# Irrigation_Controller.net
KiCad netlist of a schematic drawn in EAGLE
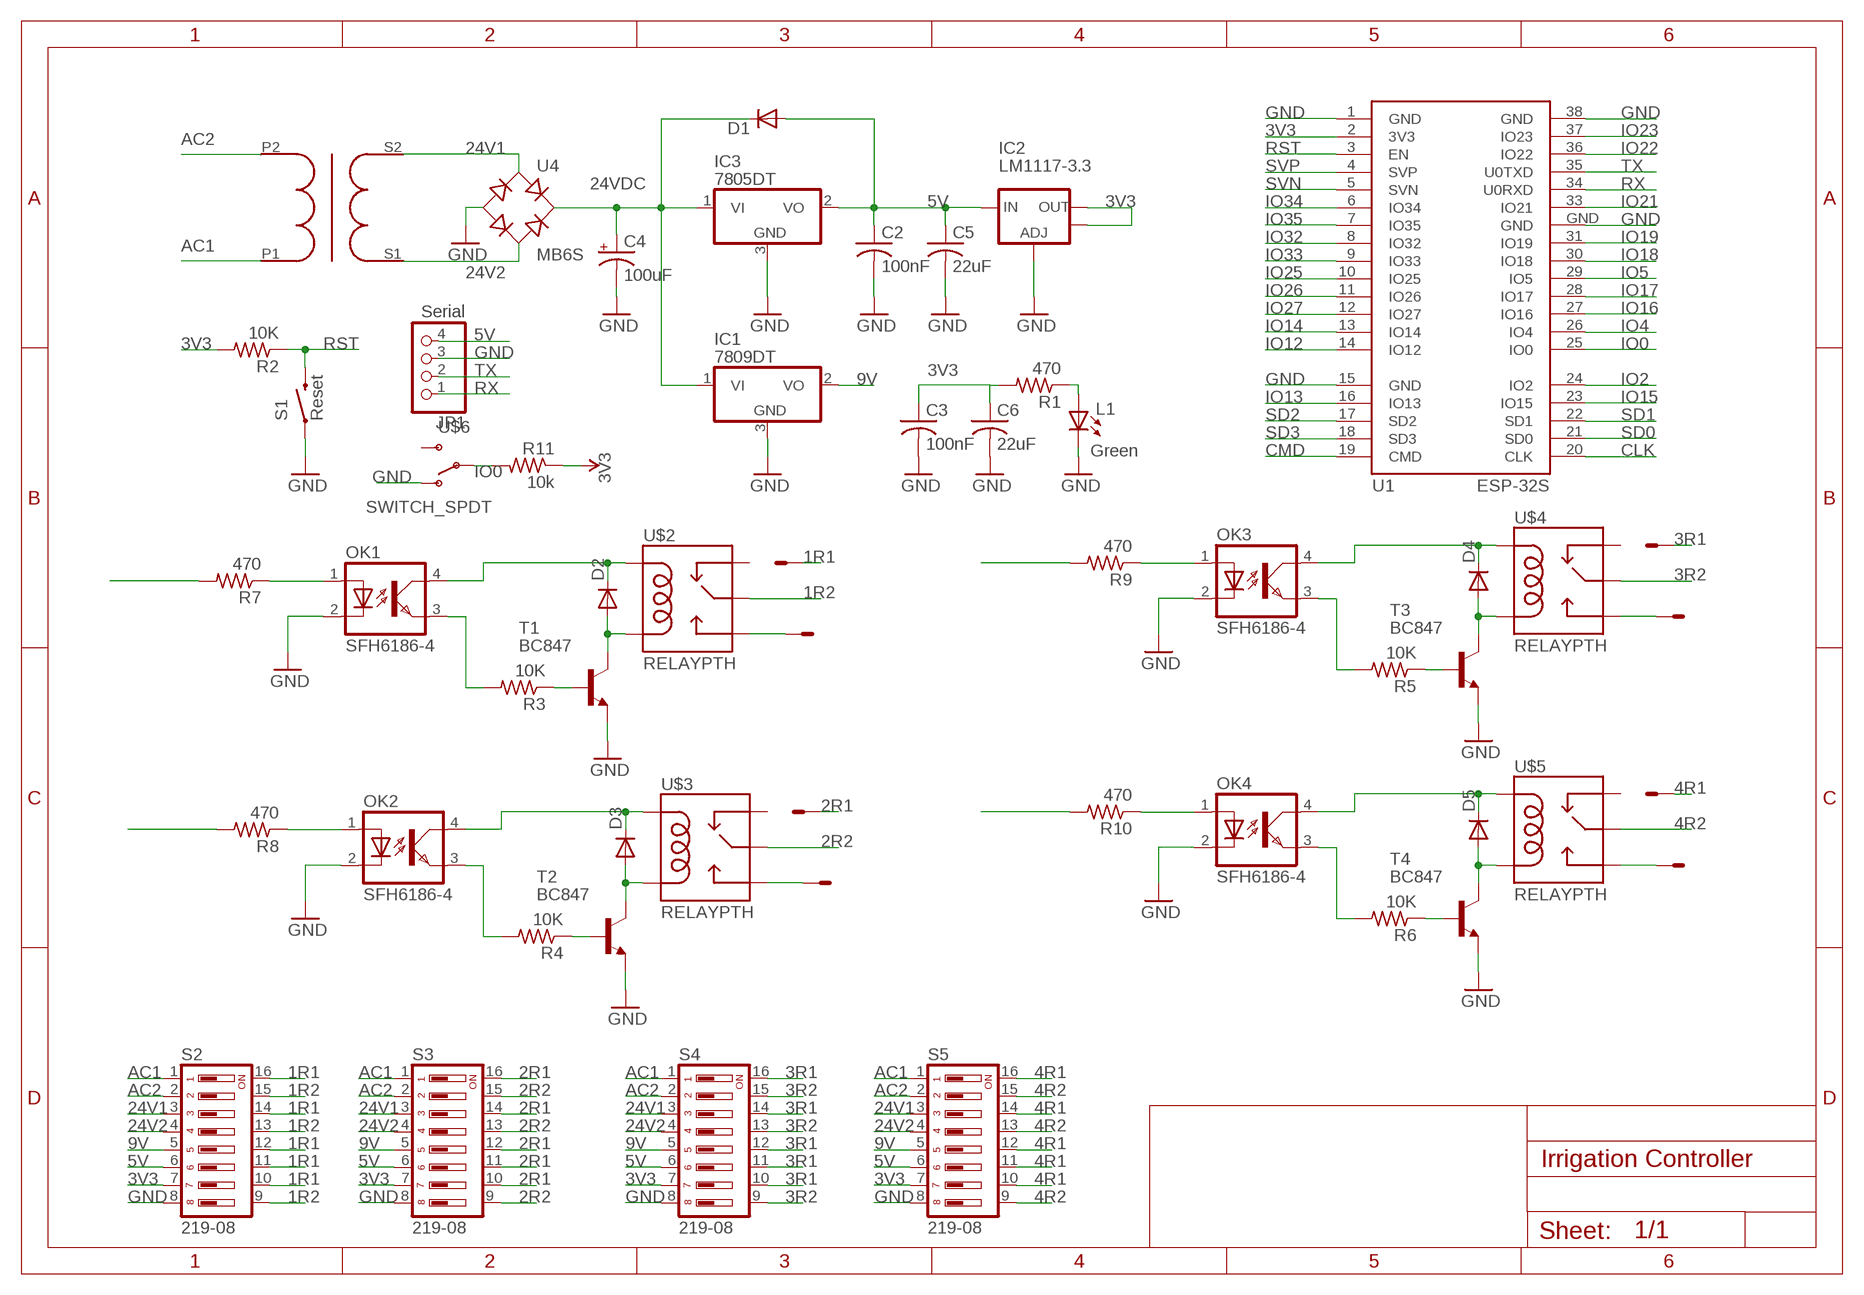
[diagram p0: schematic, sheet 1]

(export (version "E")
  (design (tool "Eeschema 10.0.6"))
  (components
    (comp (ref "C2")
      (value "100nF")
      (footprint "eagle-import:1206")
      (libsource (lib "eagle-import") (part "C1206"))
    )
    (comp (ref "C3")
      (value "100nF")
      (footprint "eagle-import:1206")
      (libsource (lib "eagle-import") (part "C1206"))
    )
    (comp (ref "C4")
      (value "100uF")
      (footprint "eagle-import:CT7343")
      (libsource (lib "eagle-import") (part "CPOL-USCT7343"))
    )
    (comp (ref "C5")
      (value "22uF")
      (footprint "eagle-import:1206")
      (libsource (lib "eagle-import") (part "C1206"))
    )
    (comp (ref "C6")
      (value "22uF")
      (footprint "eagle-import:1206")
      (libsource (lib "eagle-import") (part "C1206"))
    )
    (comp (ref "D1")
      (value "DIODE-SOD123")
      (footprint "eagle-import:SOD123")
      (libsource (lib "eagle-import") (part "DIODE-SOD123"))
    )
    (comp (ref "D2")
      (value "DIODE-SOD123")
      (footprint "eagle-import:SOD123")
      (libsource (lib "eagle-import") (part "DIODE-SOD123"))
    )
    (comp (ref "D3")
      (value "DIODE-SOD123")
      (footprint "eagle-import:SOD123")
      (libsource (lib "eagle-import") (part "DIODE-SOD123"))
    )
    (comp (ref "D4")
      (value "DIODE-SOD123")
      (footprint "eagle-import:SOD123")
      (libsource (lib "eagle-import") (part "DIODE-SOD123"))
    )
    (comp (ref "D5")
      (value "DIODE-SOD123")
      (footprint "eagle-import:SOD123")
      (libsource (lib "eagle-import") (part "DIODE-SOD123"))
    )
    (comp (ref "IC1")
      (value "7809DT")
      (footprint "eagle-import:TO252")
      (libsource (lib "eagle-import") (part "78DT05"))
    )
    (comp (ref "IC2")
      (value "LM1117-3.3")
      (footprint "eagle-import:SOT223")
      (libsource (lib "eagle-import") (part "V_REG_LM1117SOT223"))
    )
    (comp (ref "IC3")
      (value "7805DT")
      (footprint "eagle-import:TO252")
      (libsource (lib "eagle-import") (part "78DT05"))
    )
    (comp (ref "JP1")
      (value "Serial")
      (footprint "eagle-import:1X04")
      (libsource (lib "eagle-import") (part "PINHD-1X4"))
    )
    (comp (ref "L1")
      (value "Green")
      (footprint "eagle-import:LED1206")
      (libsource (lib "eagle-import") (part "LED1206"))
    )
    (comp (ref "OK1")
      (value "SFH6186-4")
      (footprint "eagle-import:SMD4-7")
      (fields (field (name "MF") "VISHAY/TELEFUNKEN"))
      (libsource (lib "eagle-import") (part "SFH618?6-4"))
    )
    (comp (ref "OK2")
      (value "SFH6186-4")
      (footprint "eagle-import:SMD4-7")
      (fields (field (name "MF") "VISHAY/TELEFUNKEN"))
      (libsource (lib "eagle-import") (part "SFH618?6-4"))
    )
    (comp (ref "OK3")
      (value "SFH6186-4")
      (footprint "eagle-import:SMD4-7")
      (fields (field (name "MF") "VISHAY/TELEFUNKEN"))
      (libsource (lib "eagle-import") (part "SFH618?6-4"))
    )
    (comp (ref "OK4")
      (value "SFH6186-4")
      (footprint "eagle-import:SMD4-7")
      (fields (field (name "MF") "VISHAY/TELEFUNKEN"))
      (libsource (lib "eagle-import") (part "SFH618?6-4"))
    )
    (comp (ref "R1")
      (value "470")
      (footprint "eagle-import:1206")
      (libsource (lib "eagle-import") (part "R1206"))
    )
    (comp (ref "R2")
      (value "10K")
      (footprint "eagle-import:R1206")
      (libsource (lib "eagle-import") (part "R-US_R1206"))
    )
    (comp (ref "R3")
      (value "10K")
      (footprint "eagle-import:R1206")
      (libsource (lib "eagle-import") (part "R-US_R1206"))
    )
    (comp (ref "R4")
      (value "10K")
      (footprint "eagle-import:R1206")
      (libsource (lib "eagle-import") (part "R-US_R1206"))
    )
    (comp (ref "R5")
      (value "10K")
      (footprint "eagle-import:R1206")
      (libsource (lib "eagle-import") (part "R-US_R1206"))
    )
    (comp (ref "R6")
      (value "10K")
      (footprint "eagle-import:R1206")
      (libsource (lib "eagle-import") (part "R-US_R1206"))
    )
    (comp (ref "R7")
      (value "470")
      (footprint "eagle-import:R1206")
      (libsource (lib "eagle-import") (part "R-US_R1206"))
    )
    (comp (ref "R8")
      (value "470")
      (footprint "eagle-import:R1206")
      (libsource (lib "eagle-import") (part "R-US_R1206"))
    )
    (comp (ref "R9")
      (value "470")
      (footprint "eagle-import:R1206")
      (libsource (lib "eagle-import") (part "R-US_R1206"))
    )
    (comp (ref "R10")
      (value "470")
      (footprint "eagle-import:R1206")
      (libsource (lib "eagle-import") (part "R-US_R1206"))
    )
    (comp (ref "R11")
      (value "10k")
      (footprint "eagle-import:1206")
      (libsource (lib "eagle-import") (part "R1206"))
    )
    (comp (ref "S1")
      (value "Reset")
      (footprint "eagle-import:TACTILE_SWITCH_TALL")
      (libsource (lib "eagle-import") (part "SWITCH-MOMENTARY-2SMD-4"))
    )
    (comp (ref "S2")
      (value "219-08")
      (footprint "eagle-import:CTS-219-08")
      (libsource (lib "eagle-import") (part "219-08"))
    )
    (comp (ref "S3")
      (value "219-08")
      (footprint "eagle-import:CTS-219-08")
      (libsource (lib "eagle-import") (part "219-08"))
    )
    (comp (ref "S4")
      (value "219-08")
      (footprint "eagle-import:CTS-219-08")
      (libsource (lib "eagle-import") (part "219-08"))
    )
    (comp (ref "S5")
      (value "219-08")
      (footprint "eagle-import:CTS-219-08")
      (libsource (lib "eagle-import") (part "219-08"))
    )
    (comp (ref "T1")
      (value "BC847")
      (footprint "eagle-import:SOT23")
      (libsource (lib "eagle-import") (part "BC847"))
    )
    (comp (ref "T2")
      (value "BC847")
      (footprint "eagle-import:SOT23")
      (libsource (lib "eagle-import") (part "BC847"))
    )
    (comp (ref "T3")
      (value "BC847")
      (footprint "eagle-import:SOT23")
      (libsource (lib "eagle-import") (part "BC847"))
    )
    (comp (ref "T4")
      (value "BC847")
      (footprint "eagle-import:SOT23")
      (libsource (lib "eagle-import") (part "BC847"))
    )
    (comp (ref "U$1")
      (value "TRANSFORMADOR_PE3010-M")
      (footprint "eagle-import:TRANSFORMADOR_PE3010-M")
      (libsource (lib "eagle-import") (part "TRANSFORMADOR_PE3010-M"))
    )
    (comp (ref "U$2")
      (value "RELAYPTH")
      (footprint "eagle-import:SRD-05VDC-SL-C")
      (libsource (lib "eagle-import") (part "RELAYPTH"))
    )
    (comp (ref "U$3")
      (value "RELAYPTH")
      (footprint "eagle-import:SRD-05VDC-SL-C")
      (libsource (lib "eagle-import") (part "RELAYPTH"))
    )
    (comp (ref "U$4")
      (value "RELAYPTH")
      (footprint "eagle-import:SRD-05VDC-SL-C")
      (libsource (lib "eagle-import") (part "RELAYPTH"))
    )
    (comp (ref "U$5")
      (value "RELAYPTH")
      (footprint "eagle-import:SRD-05VDC-SL-C")
      (libsource (lib "eagle-import") (part "RELAYPTH"))
    )
    (comp (ref "U$6")
      (value "SWITCH_SPDT")
      (footprint "eagle-import:KPS-1290")
      (libsource (lib "eagle-import") (part "SWITCH_SPDT"))
    )
    (comp (ref "U1")
      (value "ESP-32S")
      (footprint "eagle-import:ESP-32S")
      (libsource (lib "eagle-import") (part "ESP-32S"))
    )
    (comp (ref "U4")
      (value "MB6S")
      (footprint "eagle-import:SOIC-4")
      (libsource (lib "eagle-import") (part "MBS6"))
    )
    (comp (ref "X1")
      (value "22-23-2021")
      (footprint "eagle-import:22-23-2021")
      (fields (field (name "MF") "MOLEX"))
      (libsource (lib "eagle-import") (part "22-23-2021"))
    )
    (comp (ref "X2")
      (value "22-23-2021")
      (footprint "eagle-import:22-23-2021")
      (fields (field (name "MF") "MOLEX"))
      (libsource (lib "eagle-import") (part "22-23-2021"))
    )
    (comp (ref "X3")
      (value "22-23-2021")
      (footprint "eagle-import:22-23-2021")
      (fields (field (name "MF") "MOLEX"))
      (libsource (lib "eagle-import") (part "22-23-2021"))
    )
    (comp (ref "X4")
      (value "22-23-2021")
      (footprint "eagle-import:22-23-2021")
      (fields (field (name "MF") "MOLEX"))
      (libsource (lib "eagle-import") (part "22-23-2021"))
    )
  )
  (nets
    (net (code "1") (name "/1R1") (class "Default")
      (node (ref "S2") (pin "10") (pinfunction "10_10") (pintype "passive"))
      (node (ref "S2") (pin "11") (pinfunction "11_11") (pintype "passive"))
      (node (ref "S2") (pin "12") (pinfunction "12_12") (pintype "passive"))
      (node (ref "S2") (pin "14") (pinfunction "14_14") (pintype "passive"))
      (node (ref "S2") (pin "16") (pinfunction "16_16") (pintype "passive"))
      (node (ref "X1") (pin "1") (pinfunction "S_1") (pintype "passive"))
    )
    (net (code "2") (name "/1R2") (class "Default")
      (node (ref "S2") (pin "13") (pinfunction "13_13") (pintype "passive"))
      (node (ref "S2") (pin "15") (pinfunction "15_15") (pintype "passive"))
      (node (ref "S2") (pin "9") (pinfunction "9_9") (pintype "passive"))
      (node (ref "U$2") (pin "SWCOMMON") (pinfunction "SWCOMMON_SWCOMMON") (pintype "bidirectional"))
    )
    (net (code "3") (name "/2R1") (class "Default")
      (node (ref "S3") (pin "10") (pinfunction "10_10") (pintype "passive"))
      (node (ref "S3") (pin "11") (pinfunction "11_11") (pintype "passive"))
      (node (ref "S3") (pin "12") (pinfunction "12_12") (pintype "passive"))
      (node (ref "S3") (pin "14") (pinfunction "14_14") (pintype "passive"))
      (node (ref "S3") (pin "16") (pinfunction "16_16") (pintype "passive"))
      (node (ref "X2") (pin "1") (pinfunction "S_1") (pintype "passive"))
    )
    (net (code "4") (name "/2R2") (class "Default")
      (node (ref "S3") (pin "13") (pinfunction "13_13") (pintype "passive"))
      (node (ref "S3") (pin "15") (pinfunction "15_15") (pintype "passive"))
      (node (ref "S3") (pin "9") (pinfunction "9_9") (pintype "passive"))
      (node (ref "U$3") (pin "SWCOMMON") (pinfunction "SWCOMMON_SWCOMMON") (pintype "bidirectional"))
    )
    (net (code "5") (name "/3R1") (class "Default")
      (node (ref "S4") (pin "10") (pinfunction "10_10") (pintype "passive"))
      (node (ref "S4") (pin "11") (pinfunction "11_11") (pintype "passive"))
      (node (ref "S4") (pin "12") (pinfunction "12_12") (pintype "passive"))
      (node (ref "S4") (pin "14") (pinfunction "14_14") (pintype "passive"))
      (node (ref "S4") (pin "16") (pinfunction "16_16") (pintype "passive"))
      (node (ref "X3") (pin "1") (pinfunction "S_1") (pintype "passive"))
    )
    (net (code "6") (name "/3R2") (class "Default")
      (node (ref "S4") (pin "13") (pinfunction "13_13") (pintype "passive"))
      (node (ref "S4") (pin "15") (pinfunction "15_15") (pintype "passive"))
      (node (ref "S4") (pin "9") (pinfunction "9_9") (pintype "passive"))
      (node (ref "U$4") (pin "SWCOMMON") (pinfunction "SWCOMMON_SWCOMMON") (pintype "bidirectional"))
    )
    (net (code "7") (name "/4R1") (class "Default")
      (node (ref "S5") (pin "10") (pinfunction "10_10") (pintype "passive"))
      (node (ref "S5") (pin "11") (pinfunction "11_11") (pintype "passive"))
      (node (ref "S5") (pin "12") (pinfunction "12_12") (pintype "passive"))
      (node (ref "S5") (pin "14") (pinfunction "14_14") (pintype "passive"))
      (node (ref "S5") (pin "16") (pinfunction "16_16") (pintype "passive"))
      (node (ref "X4") (pin "1") (pinfunction "S_1") (pintype "passive"))
    )
    (net (code "8") (name "/4R2") (class "Default")
      (node (ref "S5") (pin "13") (pinfunction "13_13") (pintype "passive"))
      (node (ref "S5") (pin "15") (pinfunction "15_15") (pintype "passive"))
      (node (ref "S5") (pin "9") (pinfunction "9_9") (pintype "passive"))
      (node (ref "U$5") (pin "SWCOMMON") (pinfunction "SWCOMMON_SWCOMMON") (pintype "bidirectional"))
    )
    (net (code "9") (name "/5V") (class "Default")
      (node (ref "C2") (pin "1") (pinfunction "1_1") (pintype "passive"))
      (node (ref "C5") (pin "1") (pinfunction "1_1") (pintype "passive"))
      (node (ref "D1") (pin "A") (pinfunction "A_A") (pintype "passive"))
      (node (ref "IC2") (pin "3") (pinfunction "IN_3") (pintype "input"))
      (node (ref "IC3") (pin "2") (pinfunction "VO_2") (pintype "passive"))
      (node (ref "JP1") (pin "4") (pinfunction "4_4") (pintype "passive"))
      (node (ref "S2") (pin "6") (pinfunction "6_6") (pintype "passive"))
      (node (ref "S3") (pin "6") (pinfunction "6_6") (pintype "passive"))
      (node (ref "S4") (pin "6") (pinfunction "6_6") (pintype "passive"))
      (node (ref "S5") (pin "6") (pinfunction "6_6") (pintype "passive"))
    )
    (net (code "10") (name "/9V") (class "Default")
      (node (ref "IC1") (pin "2") (pinfunction "VO_2") (pintype "passive"))
      (node (ref "S2") (pin "5") (pinfunction "5_5") (pintype "passive"))
      (node (ref "S3") (pin "5") (pinfunction "5_5") (pintype "passive"))
      (node (ref "S4") (pin "5") (pinfunction "5_5") (pintype "passive"))
      (node (ref "S5") (pin "5") (pinfunction "5_5") (pintype "passive"))
    )
    (net (code "11") (name "/24V1") (class "Default")
      (node (ref "S2") (pin "3") (pinfunction "3_3") (pintype "passive"))
      (node (ref "S3") (pin "3") (pinfunction "3_3") (pintype "passive"))
      (node (ref "S4") (pin "3") (pinfunction "3_3") (pintype "passive"))
      (node (ref "S5") (pin "3") (pinfunction "3_3") (pintype "passive"))
      (node (ref "U$1") (pin "S2") (pinfunction "S2_S2") (pintype "bidirectional"))
      (node (ref "U4") (pin "~1") (pinfunction "AC1_~1") (pintype "passive"))
    )
    (net (code "12") (name "/24V2") (class "Default")
      (node (ref "S2") (pin "4") (pinfunction "4_4") (pintype "passive"))
      (node (ref "S3") (pin "4") (pinfunction "4_4") (pintype "passive"))
      (node (ref "S4") (pin "4") (pinfunction "4_4") (pintype "passive"))
      (node (ref "S5") (pin "4") (pinfunction "4_4") (pintype "passive"))
      (node (ref "U$1") (pin "S1") (pinfunction "S1_S1") (pintype "bidirectional"))
      (node (ref "U4") (pin "~2") (pinfunction "AC2_~2") (pintype "passive"))
    )
    (net (code "13") (name "/24VDC") (class "Default")
      (node (ref "C4") (pin "+") (pinfunction "+_+") (pintype "passive"))
      (node (ref "D1") (pin "C") (pinfunction "C_C") (pintype "passive"))
      (node (ref "IC1") (pin "1") (pinfunction "VI_1") (pintype "input"))
      (node (ref "IC3") (pin "1") (pinfunction "VI_1") (pintype "input"))
      (node (ref "U4") (pin "+") (pinfunction "+_+") (pintype "passive"))
    )
    (net (code "14") (name "/AC1") (class "Default")
      (node (ref "S2") (pin "1") (pinfunction "1_1") (pintype "passive"))
      (node (ref "S3") (pin "1") (pinfunction "1_1") (pintype "passive"))
      (node (ref "S4") (pin "1") (pinfunction "1_1") (pintype "passive"))
      (node (ref "S5") (pin "1") (pinfunction "1_1") (pintype "passive"))
      (node (ref "U$1") (pin "P1") (pinfunction "P1_P1") (pintype "bidirectional"))
    )
    (net (code "15") (name "/AC2") (class "Default")
      (node (ref "S2") (pin "2") (pinfunction "2_2") (pintype "passive"))
      (node (ref "S3") (pin "2") (pinfunction "2_2") (pintype "passive"))
      (node (ref "S4") (pin "2") (pinfunction "2_2") (pintype "passive"))
      (node (ref "S5") (pin "2") (pinfunction "2_2") (pintype "passive"))
      (node (ref "U$1") (pin "P2") (pinfunction "P2_P2") (pintype "bidirectional"))
    )
    (net (code "16") (name "/CLK") (class "Default")
      (node (ref "U1") (pin "20") (pinfunction "CLK_20") (pintype "bidirectional"))
    )
    (net (code "17") (name "/CMD") (class "Default")
      (node (ref "U1") (pin "19") (pinfunction "CMD_19") (pintype "bidirectional"))
    )
    (net (code "18") (name "/IO0") (class "Default")
      (node (ref "R11") (pin "2") (pinfunction "2_2") (pintype "passive"))
      (node (ref "U$6") (pin "P") (pinfunction "P_P") (pintype "passive"))
      (node (ref "U1") (pin "25") (pinfunction "IO0_25") (pintype "bidirectional"))
    )
    (net (code "19") (name "/IO2") (class "Default")
      (node (ref "U1") (pin "24") (pinfunction "IO2_24") (pintype "bidirectional"))
    )
    (net (code "20") (name "/IO4") (class "Default")
      (node (ref "U1") (pin "26") (pinfunction "IO4_26") (pintype "bidirectional"))
    )
    (net (code "21") (name "/IO5") (class "Default")
      (node (ref "U1") (pin "29") (pinfunction "IO5_29") (pintype "bidirectional"))
    )
    (net (code "22") (name "/IO12") (class "Default")
      (node (ref "U1") (pin "14") (pinfunction "IO12_14") (pintype "bidirectional"))
    )
    (net (code "23") (name "/IO13") (class "Default")
      (node (ref "U1") (pin "16") (pinfunction "IO13_16") (pintype "bidirectional"))
    )
    (net (code "24") (name "/IO14") (class "Default")
      (node (ref "U1") (pin "13") (pinfunction "IO14_13") (pintype "bidirectional"))
    )
    (net (code "25") (name "/IO15") (class "Default")
      (node (ref "U1") (pin "23") (pinfunction "IO15_23") (pintype "bidirectional"))
    )
    (net (code "26") (name "/IO16") (class "Default")
      (node (ref "U1") (pin "27") (pinfunction "IO16_27") (pintype "bidirectional"))
    )
    (net (code "27") (name "/IO17") (class "Default")
      (node (ref "U1") (pin "28") (pinfunction "IO17_28") (pintype "bidirectional"))
    )
    (net (code "28") (name "/IO18") (class "Default")
      (node (ref "U1") (pin "30") (pinfunction "IO18_30") (pintype "bidirectional"))
    )
    (net (code "29") (name "/IO19") (class "Default")
      (node (ref "U1") (pin "31") (pinfunction "IO19_31") (pintype "bidirectional"))
    )
    (net (code "30") (name "/IO21") (class "Default")
      (node (ref "U1") (pin "33") (pinfunction "IO21_33") (pintype "bidirectional"))
    )
    (net (code "31") (name "/IO22") (class "Default")
      (node (ref "U1") (pin "36") (pinfunction "IO22_36") (pintype "bidirectional"))
    )
    (net (code "32") (name "/IO23") (class "Default")
      (node (ref "U1") (pin "37") (pinfunction "IO23_37") (pintype "bidirectional"))
    )
    (net (code "33") (name "/IO25") (class "Default")
      (node (ref "U1") (pin "10") (pinfunction "IO25_10") (pintype "bidirectional"))
    )
    (net (code "34") (name "/IO26") (class "Default")
      (node (ref "U1") (pin "11") (pinfunction "IO26_11") (pintype "bidirectional"))
    )
    (net (code "35") (name "/IO27") (class "Default")
      (node (ref "U1") (pin "12") (pinfunction "IO27_12") (pintype "bidirectional"))
    )
    (net (code "36") (name "/IO32") (class "Default")
      (node (ref "U1") (pin "8") (pinfunction "IO32_8") (pintype "bidirectional"))
    )
    (net (code "37") (name "/IO33") (class "Default")
      (node (ref "U1") (pin "9") (pinfunction "IO33_9") (pintype "bidirectional"))
    )
    (net (code "38") (name "/IO34") (class "Default")
      (node (ref "U1") (pin "6") (pinfunction "IO34_6") (pintype "bidirectional"))
    )
    (net (code "39") (name "/IO35") (class "Default")
      (node (ref "U1") (pin "7") (pinfunction "IO35_7") (pintype "bidirectional"))
    )
    (net (code "40") (name "/RST") (class "Default")
      (node (ref "R2") (pin "1") (pinfunction "1_1") (pintype "passive"))
      (node (ref "S1") (pin "B2") (pinfunction "2_B2") (pintype "passive"))
      (node (ref "U1") (pin "3") (pinfunction "EN_3") (pintype "input"))
    )
    (net (code "41") (name "/RX") (class "Default")
      (node (ref "JP1") (pin "1") (pinfunction "1_1") (pintype "passive"))
      (node (ref "U1") (pin "34") (pinfunction "U0RXD_34") (pintype "bidirectional"))
    )
    (net (code "42") (name "/SD0") (class "Default")
      (node (ref "U1") (pin "21") (pinfunction "SD0_21") (pintype "bidirectional"))
    )
    (net (code "43") (name "/SD1") (class "Default")
      (node (ref "U1") (pin "22") (pinfunction "SD1_22") (pintype "bidirectional"))
    )
    (net (code "44") (name "/SD2") (class "Default")
      (node (ref "U1") (pin "17") (pinfunction "SD2_17") (pintype "bidirectional"))
    )
    (net (code "45") (name "/SD3") (class "Default")
      (node (ref "U1") (pin "18") (pinfunction "SD3_18") (pintype "bidirectional"))
    )
    (net (code "46") (name "/SVN") (class "Default")
      (node (ref "U1") (pin "5") (pinfunction "SVN_5") (pintype "bidirectional"))
    )
    (net (code "47") (name "/SVP") (class "Default")
      (node (ref "U1") (pin "4") (pinfunction "SVP_4") (pintype "bidirectional"))
    )
    (net (code "48") (name "/TX") (class "Default")
      (node (ref "JP1") (pin "2") (pinfunction "2_2") (pintype "passive"))
      (node (ref "U1") (pin "35") (pinfunction "U0TXD_35") (pintype "bidirectional"))
    )
    (net (code "49") (name "GND") (class "Default")
      (node (ref "C2") (pin "2") (pinfunction "2_2") (pintype "passive"))
      (node (ref "C3") (pin "2") (pinfunction "2_2") (pintype "passive"))
      (node (ref "C4") (pin "-") (pinfunction "-_-") (pintype "passive"))
      (node (ref "C5") (pin "2") (pinfunction "2_2") (pintype "passive"))
      (node (ref "C6") (pin "2") (pinfunction "2_2") (pintype "passive"))
      (node (ref "IC1") (pin "3") (pinfunction "GND_3") (pintype "passive"))
      (node (ref "IC2") (pin "1") (pinfunction "ADJ_1") (pintype "input"))
      (node (ref "IC3") (pin "3") (pinfunction "GND_3") (pintype "passive"))
      (node (ref "JP1") (pin "3") (pinfunction "3_3") (pintype "passive"))
      (node (ref "L1") (pin "C") (pinfunction "C_C") (pintype "passive"))
      (node (ref "OK1") (pin "2") (pinfunction "C_2") (pintype "passive"))
      (node (ref "OK2") (pin "2") (pinfunction "C_2") (pintype "passive"))
      (node (ref "OK3") (pin "2") (pinfunction "C_2") (pintype "passive"))
      (node (ref "OK4") (pin "2") (pinfunction "C_2") (pintype "passive"))
      (node (ref "S1") (pin "A2") (pinfunction "1_A2") (pintype "passive"))
      (node (ref "S2") (pin "8") (pinfunction "8_8") (pintype "passive"))
      (node (ref "S3") (pin "8") (pinfunction "8_8") (pintype "passive"))
      (node (ref "S4") (pin "8") (pinfunction "8_8") (pintype "passive"))
      (node (ref "S5") (pin "8") (pinfunction "8_8") (pintype "passive"))
      (node (ref "T1") (pin "2") (pinfunction "E_2") (pintype "passive"))
      (node (ref "T2") (pin "2") (pinfunction "E_2") (pintype "passive"))
      (node (ref "T3") (pin "2") (pinfunction "E_2") (pintype "passive"))
      (node (ref "T4") (pin "2") (pinfunction "E_2") (pintype "passive"))
      (node (ref "U$6") (pin "O") (pinfunction "O_O") (pintype "passive"))
      (node (ref "U1") (pin "1") (pinfunction "GND_1") (pintype "power_in"))
      (node (ref "U1") (pin "15") (pinfunction "GND_15") (pintype "power_in"))
      (node (ref "U1") (pin "38") (pinfunction "GND_38") (pintype "power_in"))
      (node (ref "U1") (pin "GND") (pinfunction "GND_GND") (pintype "power_in"))
      (node (ref "U4") (pin "-") (pinfunction "-_-") (pintype "passive"))
    )
    (net (code "50") (name "Net-(L1-PadA)") (class "Default")
      (node (ref "L1") (pin "A") (pinfunction "A_A") (pintype "passive"))
      (node (ref "R1") (pin "1") (pinfunction "1_1") (pintype "passive"))
    )
    (net (code "51") (name "Net-(OK1-A)") (class "Default")
      (node (ref "OK1") (pin "1") (pinfunction "A_1") (pintype "passive"))
      (node (ref "R7") (pin "1") (pinfunction "1_1") (pintype "passive"))
    )
    (net (code "52") (name "Net-(OK1-COL)") (class "Default")
      (node (ref "D2") (pin "C") (pinfunction "C_C") (pintype "passive"))
      (node (ref "OK1") (pin "4") (pinfunction "COL_4") (pintype "passive"))
      (node (ref "U$2") (pin "COIL1") (pinfunction "COIL1_COIL1") (pintype "bidirectional"))
    )
    (net (code "53") (name "Net-(OK1-EMIT)") (class "Default")
      (node (ref "OK1") (pin "3") (pinfunction "EMIT_3") (pintype "passive"))
      (node (ref "R3") (pin "2") (pinfunction "2_2") (pintype "passive"))
    )
    (net (code "54") (name "Net-(OK2-A)") (class "Default")
      (node (ref "OK2") (pin "1") (pinfunction "A_1") (pintype "passive"))
      (node (ref "R8") (pin "1") (pinfunction "1_1") (pintype "passive"))
    )
    (net (code "55") (name "Net-(OK2-COL)") (class "Default")
      (node (ref "D3") (pin "C") (pinfunction "C_C") (pintype "passive"))
      (node (ref "OK2") (pin "4") (pinfunction "COL_4") (pintype "passive"))
      (node (ref "U$3") (pin "COIL1") (pinfunction "COIL1_COIL1") (pintype "bidirectional"))
    )
    (net (code "56") (name "Net-(OK2-EMIT)") (class "Default")
      (node (ref "OK2") (pin "3") (pinfunction "EMIT_3") (pintype "passive"))
      (node (ref "R4") (pin "2") (pinfunction "2_2") (pintype "passive"))
    )
    (net (code "57") (name "Net-(OK3-A)") (class "Default")
      (node (ref "OK3") (pin "1") (pinfunction "A_1") (pintype "passive"))
      (node (ref "R9") (pin "1") (pinfunction "1_1") (pintype "passive"))
    )
    (net (code "58") (name "Net-(OK3-COL)") (class "Default")
      (node (ref "D4") (pin "C") (pinfunction "C_C") (pintype "passive"))
      (node (ref "OK3") (pin "4") (pinfunction "COL_4") (pintype "passive"))
      (node (ref "U$4") (pin "COIL1") (pinfunction "COIL1_COIL1") (pintype "bidirectional"))
    )
    (net (code "59") (name "Net-(OK3-EMIT)") (class "Default")
      (node (ref "OK3") (pin "3") (pinfunction "EMIT_3") (pintype "passive"))
      (node (ref "R5") (pin "2") (pinfunction "2_2") (pintype "passive"))
    )
    (net (code "60") (name "Net-(OK4-A)") (class "Default")
      (node (ref "OK4") (pin "1") (pinfunction "A_1") (pintype "passive"))
      (node (ref "R10") (pin "1") (pinfunction "1_1") (pintype "passive"))
    )
    (net (code "61") (name "Net-(OK4-COL)") (class "Default")
      (node (ref "D5") (pin "C") (pinfunction "C_C") (pintype "passive"))
      (node (ref "OK4") (pin "4") (pinfunction "COL_4") (pintype "passive"))
      (node (ref "U$5") (pin "COIL1") (pinfunction "COIL1_COIL1") (pintype "bidirectional"))
    )
    (net (code "62") (name "Net-(OK4-EMIT)") (class "Default")
      (node (ref "OK4") (pin "3") (pinfunction "EMIT_3") (pintype "passive"))
      (node (ref "R6") (pin "2") (pinfunction "2_2") (pintype "passive"))
    )
    (net (code "63") (name "Net-(T1-B)") (class "Default")
      (node (ref "R3") (pin "1") (pinfunction "1_1") (pintype "passive"))
      (node (ref "T1") (pin "1") (pinfunction "B_1") (pintype "passive"))
    )
    (net (code "64") (name "Net-(T1-C)") (class "Default")
      (node (ref "D2") (pin "A") (pinfunction "A_A") (pintype "passive"))
      (node (ref "T1") (pin "3") (pinfunction "C_3") (pintype "passive"))
      (node (ref "U$2") (pin "COIL0") (pinfunction "COIL0_COIL0") (pintype "bidirectional"))
    )
    (net (code "65") (name "Net-(T2-B)") (class "Default")
      (node (ref "R4") (pin "1") (pinfunction "1_1") (pintype "passive"))
      (node (ref "T2") (pin "1") (pinfunction "B_1") (pintype "passive"))
    )
    (net (code "66") (name "Net-(T2-C)") (class "Default")
      (node (ref "D3") (pin "A") (pinfunction "A_A") (pintype "passive"))
      (node (ref "T2") (pin "3") (pinfunction "C_3") (pintype "passive"))
      (node (ref "U$3") (pin "COIL0") (pinfunction "COIL0_COIL0") (pintype "bidirectional"))
    )
    (net (code "67") (name "Net-(T3-B)") (class "Default")
      (node (ref "R5") (pin "1") (pinfunction "1_1") (pintype "passive"))
      (node (ref "T3") (pin "1") (pinfunction "B_1") (pintype "passive"))
    )
    (net (code "68") (name "Net-(T3-C)") (class "Default")
      (node (ref "D4") (pin "A") (pinfunction "A_A") (pintype "passive"))
      (node (ref "T3") (pin "3") (pinfunction "C_3") (pintype "passive"))
      (node (ref "U$4") (pin "COIL0") (pinfunction "COIL0_COIL0") (pintype "bidirectional"))
    )
    (net (code "69") (name "Net-(T4-B)") (class "Default")
      (node (ref "R6") (pin "1") (pinfunction "1_1") (pintype "passive"))
      (node (ref "T4") (pin "1") (pinfunction "B_1") (pintype "passive"))
    )
    (net (code "70") (name "Net-(T4-C)") (class "Default")
      (node (ref "D5") (pin "A") (pinfunction "A_A") (pintype "passive"))
      (node (ref "T4") (pin "3") (pinfunction "C_3") (pintype "passive"))
      (node (ref "U$5") (pin "COIL0") (pinfunction "COIL0_COIL0") (pintype "bidirectional"))
    )
    (net (code "71") (name "Net-(X1B-S)") (class "Default")
      (node (ref "U$2") (pin "SWOPEN") (pinfunction "SWOPEN_SWOPEN") (pintype "bidirectional"))
      (node (ref "X1") (pin "2") (pinfunction "S_2") (pintype "passive"))
    )
    (net (code "72") (name "Net-(X2B-S)") (class "Default")
      (node (ref "U$3") (pin "SWOPEN") (pinfunction "SWOPEN_SWOPEN") (pintype "bidirectional"))
      (node (ref "X2") (pin "2") (pinfunction "S_2") (pintype "passive"))
    )
    (net (code "73") (name "Net-(X3B-S)") (class "Default")
      (node (ref "U$4") (pin "SWOPEN") (pinfunction "SWOPEN_SWOPEN") (pintype "bidirectional"))
      (node (ref "X3") (pin "2") (pinfunction "S_2") (pintype "passive"))
    )
    (net (code "74") (name "Net-(X4B-S)") (class "Default")
      (node (ref "U$5") (pin "SWOPEN") (pinfunction "SWOPEN_SWOPEN") (pintype "bidirectional"))
      (node (ref "X4") (pin "2") (pinfunction "S_2") (pintype "passive"))
    )
    (net (code "75") (name "VCC") (class "Default")
      (node (ref "C3") (pin "1") (pinfunction "1_1") (pintype "passive"))
      (node (ref "C6") (pin "1") (pinfunction "1_1") (pintype "passive"))
      (node (ref "IC2") (pin "2") (pinfunction "OUT_2") (pintype "output"))
      (node (ref "IC2") (pin "4") (pinfunction "OUT_4") (pintype "output"))
      (node (ref "R1") (pin "2") (pinfunction "2_2") (pintype "passive"))
      (node (ref "R11") (pin "1") (pinfunction "1_1") (pintype "passive"))
      (node (ref "R2") (pin "2") (pinfunction "2_2") (pintype "passive"))
      (node (ref "S2") (pin "7") (pinfunction "7_7") (pintype "passive"))
      (node (ref "S3") (pin "7") (pinfunction "7_7") (pintype "passive"))
      (node (ref "S4") (pin "7") (pinfunction "7_7") (pintype "passive"))
      (node (ref "S5") (pin "7") (pinfunction "7_7") (pintype "passive"))
      (node (ref "U1") (pin "2") (pinfunction "3V3_2") (pintype "power_in"))
    )
    (net (code "76") (name "unconnected-(R7-Pad2)") (class "Default")
      (node (ref "R7") (pin "2") (pinfunction "2_2") (pintype "passive"))
    )
    (net (code "77") (name "unconnected-(R8-Pad2)") (class "Default")
      (node (ref "R8") (pin "2") (pinfunction "2_2") (pintype "passive"))
    )
    (net (code "78") (name "unconnected-(R9-Pad2)") (class "Default")
      (node (ref "R9") (pin "2") (pinfunction "2_2") (pintype "passive"))
    )
    (net (code "79") (name "unconnected-(R10-Pad2)") (class "Default")
      (node (ref "R10") (pin "2") (pinfunction "2_2") (pintype "passive"))
    )
    (net (code "80") (name "unconnected-(U$2-SWCLOSE-PadSWCLOSED)") (class "Default")
      (node (ref "U$2") (pin "SWCLOSED") (pinfunction "SWCLOSE_SWCLOSED") (pintype "bidirectional"))
    )
    (net (code "81") (name "unconnected-(U$3-SWCLOSE-PadSWCLOSED)") (class "Default")
      (node (ref "U$3") (pin "SWCLOSED") (pinfunction "SWCLOSE_SWCLOSED") (pintype "bidirectional"))
    )
    (net (code "82") (name "unconnected-(U$4-SWCLOSE-PadSWCLOSED)") (class "Default")
      (node (ref "U$4") (pin "SWCLOSED") (pinfunction "SWCLOSE_SWCLOSED") (pintype "bidirectional"))
    )
    (net (code "83") (name "unconnected-(U$5-SWCLOSE-PadSWCLOSED)") (class "Default")
      (node (ref "U$5") (pin "SWCLOSED") (pinfunction "SWCLOSE_SWCLOSED") (pintype "bidirectional"))
    )
    (net (code "84") (name "unconnected-(U$6-PadS)") (class "Default")
      (node (ref "U$6") (pin "S") (pinfunction "S_S") (pintype "passive"))
    )
  )
)
